# Temp_Supervisor.net
KiCad netlist of a schematic drawn in Altium Designer
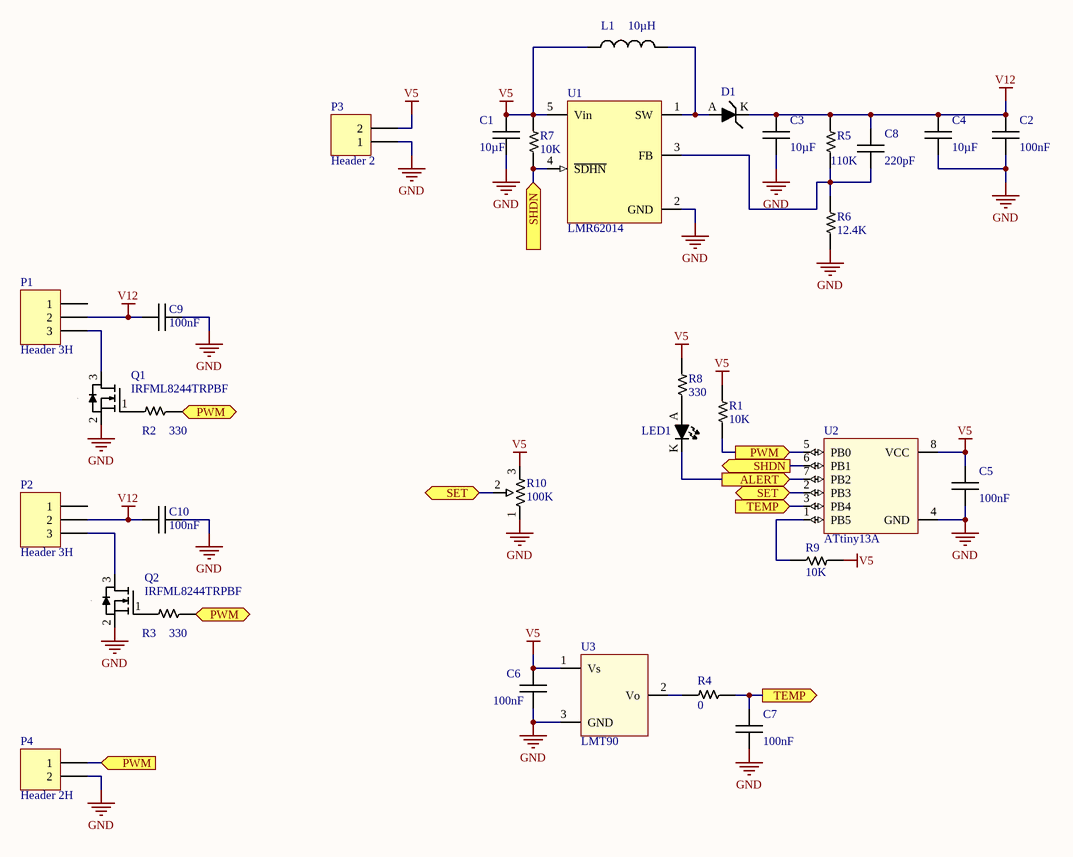
[diagram p0: Temp Supervisor.SchDoc]

(export (version "E")
  (design (tool "Eeschema 10.0.6"))
  (components
    (comp (ref "C1")
      (value "10µF")
      (footprint "CAPC2012N")
      (fields (field (name "VOLTAGE") "24V"))
      (libsource (lib "Megaxone") (part "Capacitor"))
    )
    (comp (ref "C2")
      (value "100nF")
      (footprint "CAPC1608N")
      (fields (field (name "VOLTAGE") "24V"))
      (libsource (lib "Megaxone") (part "Capacitor"))
    )
    (comp (ref "C3")
      (value "10µF")
      (footprint "CAPC2012N")
      (fields (field (name "VOLTAGE") "24V"))
      (libsource (lib "Megaxone") (part "Capacitor"))
    )
    (comp (ref "C4")
      (value "10µF")
      (footprint "CAPC2012N")
      (fields (field (name "VOLTAGE") "24V"))
      (libsource (lib "Megaxone") (part "Capacitor"))
    )
    (comp (ref "C5")
      (value "100nF")
      (footprint "CAPC1608N")
      (fields (field (name "VOLTAGE") "24V"))
      (libsource (lib "Megaxone") (part "Capacitor"))
    )
    (comp (ref "C6")
      (value "100nF")
      (footprint "CAPC1608N")
      (fields (field (name "VOLTAGE") "24V"))
      (libsource (lib "Megaxone") (part "Capacitor"))
    )
    (comp (ref "C7")
      (value "100nF")
      (footprint "CAPC1608N")
      (fields (field (name "VOLTAGE") "24V"))
      (libsource (lib "Megaxone") (part "Capacitor"))
    )
    (comp (ref "C8")
      (value "220pF")
      (footprint "CAPC1608N")
      (fields (field (name "VOLTAGE") "24V"))
      (libsource (lib "Megaxone") (part "Capacitor"))
    )
    (comp (ref "C9")
      (value "100nF")
      (footprint "CAPC1608N")
      (fields (field (name "VOLTAGE") "24V"))
      (libsource (lib "Megaxone") (part "Capacitor"))
    )
    (comp (ref "C10")
      (value "100nF")
      (footprint "CAPC1608N")
      (fields (field (name "VOLTAGE") "24V"))
      (libsource (lib "Megaxone") (part "Capacitor"))
    )
    (comp (ref "D1") (value "~") (footprint "DO-214AC") (libsource (lib "Megaxone") (part "Diode Schottky")))
    (comp (ref "L1")
      (value "10µH")
      (footprint "INDUCTOR 6×6mm Taiyo Yuden")
      (libsource (lib "Megaxone") (part "Inductor"))
    )
    (comp (ref "LED1") (value "~") (footprint "LED 3216m") (libsource (lib "Megaxone") (part "LED")))
    (comp (ref "P1")
      (value "Header 3H")
      (footprint "HDR1X3H")
      (description "Header, 3-Pin, Right Angle")
      (fields (field (name "PUBLISHER") "Altium Limited"))
      (libsource (lib "Miscellaneous Connectors") (part "Header 3H"))
    )
    (comp (ref "P2")
      (value "Header 3H")
      (footprint "HDR1X3H")
      (description "Header, 3-Pin, Right Angle")
      (fields (field (name "PUBLISHER") "Altium Limited"))
      (libsource (lib "Miscellaneous Connectors") (part "Header 3H"))
    )
    (comp (ref "P3")
      (value "Header 2")
      (footprint "HDR1X2")
      (description "Header, 2-Pin")
      (fields (field (name "PUBLISHER") "Altium Limited"))
      (libsource (lib "Miscellaneous Connectors") (part "Header 2"))
    )
    (comp (ref "P4")
      (value "Header 2H")
      (footprint "HDR1X2H")
      (description "Header, 2-Pin, Right Angle")
      (fields (field (name "PUBLISHER") "Altium Limited"))
      (libsource (lib "Miscellaneous Connectors") (part "Header 2H"))
    )
    (comp (ref "Q1")
      (value "IRFML8244TRPBF")
      (footprint "SOT23-3N")
      (libsource (lib "Megaxone") (part "MOSFET N-Ch enh"))
    )
    (comp (ref "Q2")
      (value "IRFML8244TRPBF")
      (footprint "SOT23-3N")
      (libsource (lib "Megaxone") (part "MOSFET N-Ch enh"))
    )
    (comp (ref "R1") (value "10K") (footprint "RESC1608N") (libsource (lib "Megaxone") (part "Resistor")))
    (comp (ref "R2") (value "330") (footprint "RESC1608N") (libsource (lib "") (part "Resistor_1")))
    (comp (ref "R3") (value "330") (footprint "RESC1608N") (libsource (lib "") (part "Resistor_1")))
    (comp (ref "R4") (value "0") (footprint "RESC1608N") (libsource (lib "") (part "Resistor_1")))
    (comp (ref "R5") (value "110K") (footprint "RESC1608N") (libsource (lib "Megaxone") (part "Resistor")))
    (comp (ref "R6") (value "12.4K") (footprint "RESC1608N") (libsource (lib "Megaxone") (part "Resistor")))
    (comp (ref "R7") (value "10K") (footprint "RESC1608N") (libsource (lib "Megaxone") (part "Resistor")))
    (comp (ref "R8") (value "330") (footprint "RESC1608N") (libsource (lib "Megaxone") (part "Resistor")))
    (comp (ref "R9") (value "10K") (footprint "RESC1608N") (libsource (lib "") (part "Resistor_2")))
    (comp (ref "R10")
      (value "100K")
      (footprint "Trim-Pot 2mm SMD")
      (libsource (lib "Megaxone") (part "Potentiometer"))
    )
    (comp (ref "U1")
      (value "LMR62014")
      (footprint "SOT23-5AN")
      (libsource (lib "Megaxone") (part "LMR62014"))
    )
    (comp (ref "U2")
      (value "ATtiny13A")
      (footprint "SOIC127P600-8AN")
      (libsource (lib "Megaxone") (part "ATtiny13A"))
    )
    (comp (ref "U3") (value "LMT90") (footprint "SOT23-3N") (libsource (lib "Megaxone") (part "LMT90")))
  )
  (nets
    (net (code "1") (name "/ALERT") (class "Default")
      (node (ref "LED1") (pin "K") (pinfunction "K_K") (pintype "passive"))
      (node (ref "U2") (pin "7") (pinfunction "PB2_7") (pintype "bidirectional"))
    )
    (net (code "2") (name "/PWM") (class "Default")
      (node (ref "P4") (pin "1") (pinfunction "1_1") (pintype "passive"))
      (node (ref "R1") (pin "1") (pinfunction "1_1") (pintype "passive"))
      (node (ref "R2") (pin "1") (pinfunction "1_1") (pintype "passive"))
      (node (ref "R3") (pin "1") (pinfunction "1_1") (pintype "passive"))
      (node (ref "U2") (pin "5") (pinfunction "PB0_5") (pintype "bidirectional"))
    )
    (net (code "3") (name "/SET") (class "Default")
      (node (ref "R10") (pin "2") (pinfunction "2_2") (pintype "passive"))
      (node (ref "U2") (pin "2") (pinfunction "PB3_2") (pintype "bidirectional"))
    )
    (net (code "4") (name "/SHDN") (class "Default")
      (node (ref "R7") (pin "1") (pinfunction "1_1") (pintype "passive"))
      (node (ref "U1") (pin "4") (pinfunction "~{SDHN}_4") (pintype "input"))
      (node (ref "U2") (pin "6") (pinfunction "PB1_6") (pintype "bidirectional"))
    )
    (net (code "5") (name "/TEMP") (class "Default")
      (node (ref "C7") (pin "2") (pinfunction "2_2") (pintype "passive"))
      (node (ref "R4") (pin "1") (pinfunction "1_1") (pintype "passive"))
      (node (ref "U2") (pin "3") (pinfunction "PB4_3") (pintype "bidirectional"))
    )
    (net (code "6") (name "GND") (class "Default")
      (node (ref "C1") (pin "1") (pinfunction "1_1") (pintype "passive"))
      (node (ref "C10") (pin "1") (pinfunction "1_1") (pintype "passive"))
      (node (ref "C2") (pin "1") (pinfunction "1_1") (pintype "passive"))
      (node (ref "C3") (pin "1") (pinfunction "1_1") (pintype "passive"))
      (node (ref "C4") (pin "1") (pinfunction "1_1") (pintype "passive"))
      (node (ref "C5") (pin "1") (pinfunction "1_1") (pintype "passive"))
      (node (ref "C6") (pin "1") (pinfunction "1_1") (pintype "passive"))
      (node (ref "C7") (pin "1") (pinfunction "1_1") (pintype "passive"))
      (node (ref "C9") (pin "1") (pinfunction "1_1") (pintype "passive"))
      (node (ref "P3") (pin "1") (pinfunction "1_1") (pintype "passive"))
      (node (ref "P4") (pin "2") (pinfunction "2_2") (pintype "passive"))
      (node (ref "Q1") (pin "2") (pinfunction "S_2") (pintype "passive"))
      (node (ref "Q2") (pin "2") (pinfunction "S_2") (pintype "passive"))
      (node (ref "R10") (pin "1") (pinfunction "1_1") (pintype "passive"))
      (node (ref "R6") (pin "1") (pinfunction "1_1") (pintype "passive"))
      (node (ref "U1") (pin "2") (pinfunction "GND_2") (pintype "power_in"))
      (node (ref "U2") (pin "4") (pinfunction "GND_4") (pintype "power_in"))
      (node (ref "U3") (pin "3") (pinfunction "GND_3") (pintype "power_in"))
    )
    (net (code "7") (name "Net-(D1-Anode)") (class "Default")
      (node (ref "D1") (pin "A") (pinfunction "Anode_A") (pintype "power_in"))
      (node (ref "L1") (pin "2") (pinfunction "2_2") (pintype "passive"))
      (node (ref "U1") (pin "1") (pinfunction "SW_1") (pintype "power_in"))
    )
    (net (code "8") (name "Net-(LED1-PadA)") (class "Default")
      (node (ref "LED1") (pin "A") (pinfunction "A_A") (pintype "passive"))
      (node (ref "R8") (pin "1") (pinfunction "1_1") (pintype "passive"))
    )
    (net (code "9") (name "Net-(Q1-D)") (class "Default")
      (node (ref "P1") (pin "3") (pinfunction "3_3") (pintype "passive"))
      (node (ref "Q1") (pin "3") (pinfunction "D_3") (pintype "passive"))
    )
    (net (code "10") (name "Net-(Q1-G)") (class "Default")
      (node (ref "Q1") (pin "1") (pinfunction "G_1") (pintype "passive"))
      (node (ref "R2") (pin "2") (pinfunction "2_2") (pintype "passive"))
    )
    (net (code "11") (name "Net-(Q2-D)") (class "Default")
      (node (ref "P2") (pin "3") (pinfunction "3_3") (pintype "passive"))
      (node (ref "Q2") (pin "3") (pinfunction "D_3") (pintype "passive"))
    )
    (net (code "12") (name "Net-(Q2-G)") (class "Default")
      (node (ref "Q2") (pin "1") (pinfunction "G_1") (pintype "passive"))
      (node (ref "R3") (pin "2") (pinfunction "2_2") (pintype "passive"))
    )
    (net (code "13") (name "Net-(U1-FB)") (class "Default")
      (node (ref "C8") (pin "1") (pinfunction "1_1") (pintype "passive"))
      (node (ref "R5") (pin "1") (pinfunction "1_1") (pintype "passive"))
      (node (ref "R6") (pin "2") (pinfunction "2_2") (pintype "passive"))
      (node (ref "U1") (pin "3") (pinfunction "FB_3") (pintype "passive"))
    )
    (net (code "14") (name "Net-(U2-PB5)") (class "Default")
      (node (ref "R9") (pin "1") (pinfunction "1_1") (pintype "passive"))
      (node (ref "U2") (pin "1") (pinfunction "PB5_1") (pintype "bidirectional"))
    )
    (net (code "15") (name "Net-(U3-Vo)") (class "Default")
      (node (ref "R4") (pin "2") (pinfunction "2_2") (pintype "passive"))
      (node (ref "U3") (pin "2") (pinfunction "Vo_2") (pintype "passive"))
    )
    (net (code "16") (name "V5") (class "Default")
      (node (ref "C1") (pin "2") (pinfunction "2_2") (pintype "passive"))
      (node (ref "C5") (pin "2") (pinfunction "2_2") (pintype "passive"))
      (node (ref "C6") (pin "2") (pinfunction "2_2") (pintype "passive"))
      (node (ref "L1") (pin "1") (pinfunction "1_1") (pintype "passive"))
      (node (ref "P3") (pin "2") (pinfunction "2_2") (pintype "passive"))
      (node (ref "R1") (pin "2") (pinfunction "2_2") (pintype "passive"))
      (node (ref "R10") (pin "3") (pinfunction "3_3") (pintype "passive"))
      (node (ref "R7") (pin "2") (pinfunction "2_2") (pintype "passive"))
      (node (ref "R8") (pin "2") (pinfunction "2_2") (pintype "passive"))
      (node (ref "R9") (pin "2") (pinfunction "2_2") (pintype "passive"))
      (node (ref "U1") (pin "5") (pinfunction "Vin_5") (pintype "power_in"))
      (node (ref "U2") (pin "8") (pinfunction "VCC_8") (pintype "power_in"))
      (node (ref "U3") (pin "1") (pinfunction "Vs_1") (pintype "power_in"))
    )
    (net (code "17") (name "V12") (class "Default")
      (node (ref "C10") (pin "2") (pinfunction "2_2") (pintype "passive"))
      (node (ref "C2") (pin "2") (pinfunction "2_2") (pintype "passive"))
      (node (ref "C3") (pin "2") (pinfunction "2_2") (pintype "passive"))
      (node (ref "C4") (pin "2") (pinfunction "2_2") (pintype "passive"))
      (node (ref "C8") (pin "2") (pinfunction "2_2") (pintype "passive"))
      (node (ref "C9") (pin "2") (pinfunction "2_2") (pintype "passive"))
      (node (ref "D1") (pin "K") (pinfunction "Kathode_K") (pintype "power_in"))
      (node (ref "P1") (pin "2") (pinfunction "2_2") (pintype "passive"))
      (node (ref "P2") (pin "2") (pinfunction "2_2") (pintype "passive"))
      (node (ref "R5") (pin "2") (pinfunction "2_2") (pintype "passive"))
    )
    (net (code "18") (name "unconnected-(P1-Pad1)") (class "Default")
      (node (ref "P1") (pin "1") (pinfunction "1_1") (pintype "passive"))
    )
    (net (code "19") (name "unconnected-(P2-Pad1)") (class "Default")
      (node (ref "P2") (pin "1") (pinfunction "1_1") (pintype "passive"))
    )
  )
)
